# dht22.net
KiCad netlist of a schematic drawn in EAGLE
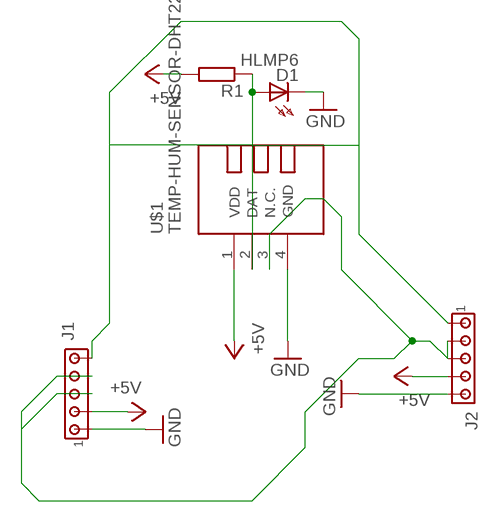
[diagram p0: schematic, sheet 1]

(export (version "E")
  (design (tool "Eeschema 10.0.6"))
  (components
    (comp (ref "D1")
      (value "HLMP6")
      (footprint "eagle-import:HLMP6")
      (fields (field (name "MF") "AGILENT TECHNOLOGIES") (field (name "MPN") "HLMP-6500"))
      (libsource (lib "eagle-import") (part "HLMP6"))
    )
    (comp (ref "J1")
      (value "MTA05-100")
      (footprint "eagle-import:10X05MTA")
      (libsource (lib "eagle-import") (part "MTA05-100"))
    )
    (comp (ref "J2")
      (value "MTA05-100")
      (footprint "eagle-import:10X05MTA")
      (libsource (lib "eagle-import") (part "MTA05-100"))
    )
    (comp (ref "R1")
      (value "R-EU_0309/10")
      (footprint "eagle-import:0309_10")
      (libsource (lib "eagle-import") (part "R-EU_0309/10"))
    )
    (comp (ref "U$1")
      (value "TEMP-HUM-SENSOR-DHT22")
      (footprint "eagle-import:TEMP-HUM-SENSOR-DHT22")
      (libsource (lib "eagle-import") (part "TEMP-HUM-SENSOR-DHT22"))
    )
  )
  (nets
    (net (code "1") (name "+5V") (class "Default")
      (node (ref "J1") (pin "2") (pinfunction "2_2") (pintype "passive"))
      (node (ref "J2") (pin "4") (pinfunction "4_4") (pintype "passive"))
      (node (ref "R1") (pin "2") (pinfunction "2_2") (pintype "passive"))
      (node (ref "U$1") (pin "1") (pinfunction "VDD_1") (pintype "power_in"))
    )
    (net (code "2") (name "GND") (class "Default")
      (node (ref "D1") (pin "K") (pinfunction "K_K") (pintype "passive"))
      (node (ref "J1") (pin "1") (pinfunction "1_1") (pintype "passive"))
      (node (ref "J2") (pin "5") (pinfunction "5_5") (pintype "passive"))
      (node (ref "U$1") (pin "4") (pinfunction "GND_4") (pintype "power_in"))
    )
    (net (code "3") (name "Net-(U$1-DAT)") (class "Default")
      (node (ref "D1") (pin "A") (pinfunction "A_A") (pintype "passive"))
      (node (ref "J1") (pin "5") (pinfunction "5_5") (pintype "passive"))
      (node (ref "J2") (pin "1") (pinfunction "1_1") (pintype "passive"))
      (node (ref "R1") (pin "1") (pinfunction "1_1") (pintype "passive"))
      (node (ref "U$1") (pin "2") (pinfunction "DAT_2") (pintype "bidirectional"))
    )
    (net (code "4") (name "Net-(U$1-N.C.)") (class "Default")
      (node (ref "J1") (pin "3") (pinfunction "3_3") (pintype "passive"))
      (node (ref "J1") (pin "4") (pinfunction "4_4") (pintype "passive"))
      (node (ref "J2") (pin "2") (pinfunction "2_2") (pintype "passive"))
      (node (ref "J2") (pin "3") (pinfunction "3_3") (pintype "passive"))
      (node (ref "U$1") (pin "3") (pinfunction "N.C._3") (pintype "passive"))
    )
  )
)
